# basestation_nbiot.net
KiCad netlist of a schematic drawn in EAGLE
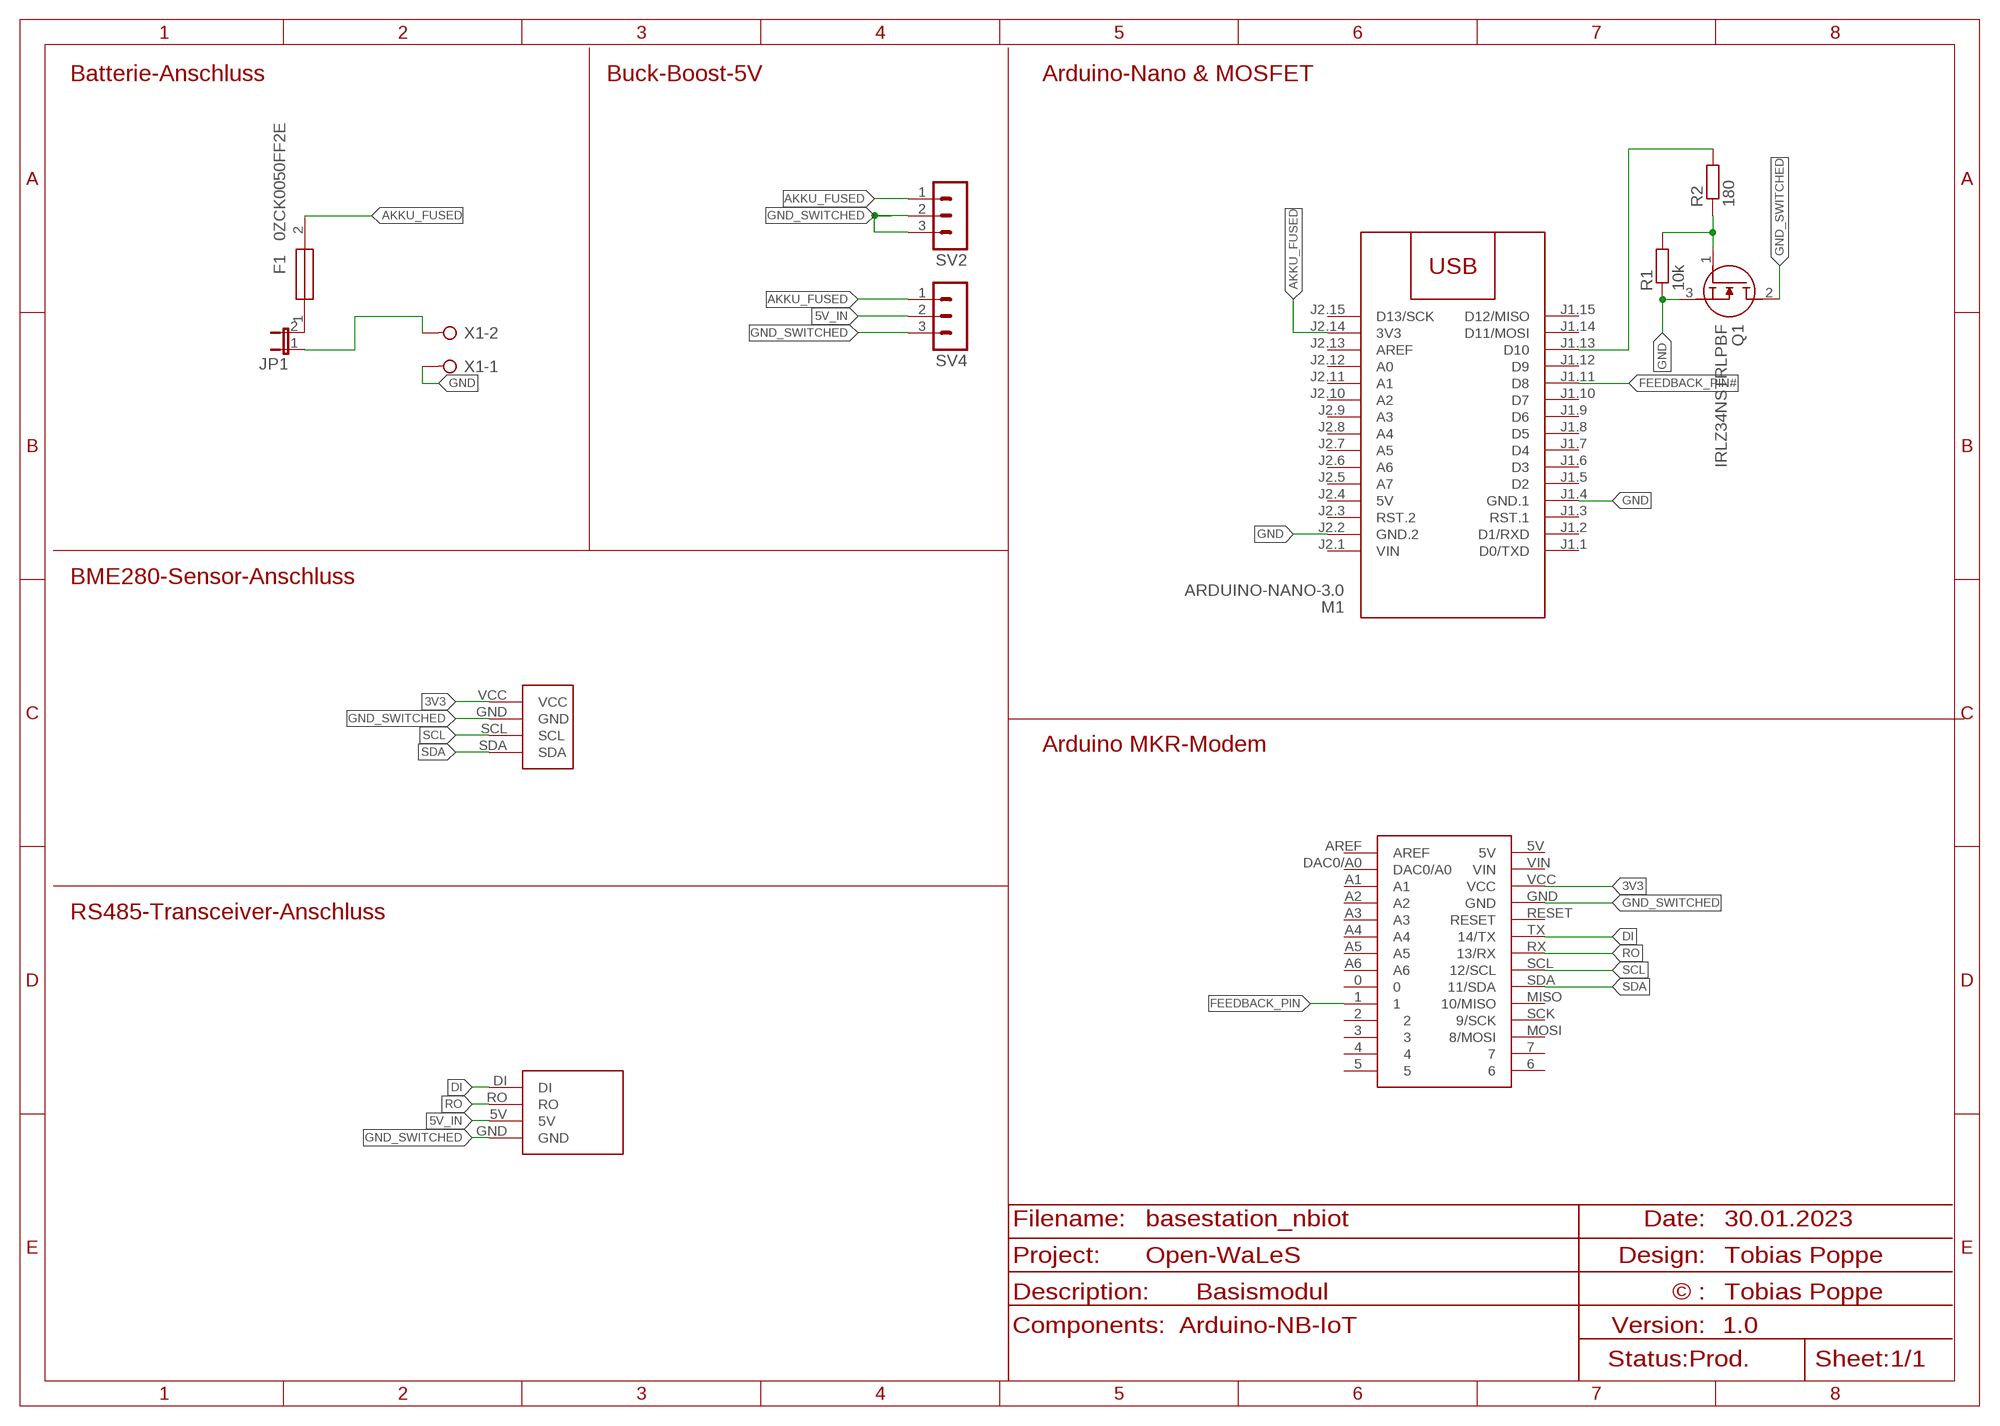
[diagram p0: schematic, sheet 1]

(export (version "E")
  (design (tool "Eeschema 10.0.6"))
  (components
    (comp (ref "F1")
      (value "0ZCK0050FF2E")
      (footprint "eagle-import:FUSC2214X125N")
      (libsource (lib "eagle-import") (part "0ZCK0050FF2E"))
    )
    (comp (ref "JP1")
      (value "JP1E")
      (footprint "eagle-import:JP1")
      (libsource (lib "eagle-import") (part "JP1E"))
    )
    (comp (ref "M1")
      (value "ARDUINO-NANO-3.0")
      (footprint "eagle-import:ARDUINO-NANO-3.0")
      (libsource (lib "eagle-import") (part "ARDUINO-NANO-3.0"))
    )
    (comp (ref "Q1")
      (value "IRLZ34NSTRLPBF")
      (footprint "eagle-import:D2PAK")
      (fields (field (name "MOUSER_PART_NUMBER") "942-IRLZ34NSTRLPBF"))
      (libsource (lib "eagle-import") (part "IRLZ34NSTRLPBF"))
    )
    (comp (ref "R1")
      (value "10k")
      (footprint "eagle-import:R1206")
      (libsource (lib "eagle-import") (part "R-EU_R1206"))
    )
    (comp (ref "R2")
      (value "180")
      (footprint "eagle-import:R1206")
      (libsource (lib "eagle-import") (part "R-EU_R1206"))
    )
    (comp (ref "SV2")
      (value "MA03-1")
      (footprint "eagle-import:MA03-1")
      (libsource (lib "eagle-import") (part "MA03-1"))
    )
    (comp (ref "SV4")
      (value "MA03-1")
      (footprint "eagle-import:MA03-1")
      (libsource (lib "eagle-import") (part "MA03-1"))
    )
    (comp (ref "U$1")
      (value "ARDUINO_GSM_MKR_1400")
      (footprint "eagle-import:ARDUINO_GSM_MKR1400")
      (libsource (lib "eagle-import") (part "ARDUINO_GSM_MKR_1400"))
    )
    (comp (ref "U$2")
      (value "BME280-BREAKOUT")
      (footprint "eagle-import:BME280-BREAKOUT")
      (libsource (lib "eagle-import") (part "BME280-BREAKOUT"))
    )
    (comp (ref "U$3")
      (value "RS485_PEGEL_BREAKOUT")
      (footprint "eagle-import:RS485_PEGEL_BREAKOUT")
      (libsource (lib "eagle-import") (part "RS485_PEGEL_BREAKOUT"))
    )
    (comp (ref "X1")
      (value "W237-02P")
      (footprint "eagle-import:W237-132")
      (libsource (lib "eagle-import") (part "W237-02P"))
    )
  )
  (nets
    (net (code "1") (name "/5V") (class "Default")
      (node (ref "M1") (pin "J2.4") (pinfunction "5V_J2.4") (pintype "power_in"))
    )
    (net (code "2") (name "/VIN") (class "Default")
      (node (ref "M1") (pin "J2.1") (pinfunction "VIN_J2.1") (pintype "power_in"))
    )
    (net (code "3") (name "3V3") (class "Default")
      (node (ref "U$1") (pin "VCC") (pinfunction "VCC_VCC") (pintype "bidirectional"))
      (node (ref "U$2") (pin "VCC") (pinfunction "VCC_VCC") (pintype "bidirectional"))
    )
    (net (code "4") (name "5V_IN") (class "Default")
      (node (ref "SV4") (pin "2") (pinfunction "2_2") (pintype "passive"))
      (node (ref "U$3") (pin "5V") (pinfunction "5V_5V") (pintype "bidirectional"))
    )
    (net (code "5") (name "AKKU_FUSED") (class "Default")
      (node (ref "F1") (pin "2") (pinfunction "2_2") (pintype "bidirectional"))
      (node (ref "M1") (pin "J2.14") (pinfunction "3V3_J2.14") (pintype "power_in"))
      (node (ref "SV2") (pin "1") (pinfunction "1_1") (pintype "passive"))
      (node (ref "SV4") (pin "1") (pinfunction "1_1") (pintype "passive"))
    )
    (net (code "6") (name "DI") (class "Default")
      (node (ref "U$1") (pin "TX") (pinfunction "14/TX_TX") (pintype "bidirectional"))
      (node (ref "U$3") (pin "DI") (pinfunction "DI_DI") (pintype "bidirectional"))
    )
    (net (code "7") (name "FEEDBACK_PIN") (class "Default")
      (node (ref "U$1") (pin "1") (pinfunction "1_1") (pintype "bidirectional"))
    )
    (net (code "8") (name "FEEDBACK_PIN#") (class "Default")
      (node (ref "M1") (pin "J1.11") (pinfunction "D8_J1.11") (pintype "bidirectional"))
    )
    (net (code "9") (name "GND") (class "Default")
      (node (ref "M1") (pin "J1.4") (pinfunction "GND.1_J1.4") (pintype "power_in"))
      (node (ref "M1") (pin "J2.2") (pinfunction "GND.2_J2.2") (pintype "power_in"))
      (node (ref "Q1") (pin "3") (pinfunction "S_3") (pintype "bidirectional"))
      (node (ref "R1") (pin "1") (pinfunction "1_1") (pintype "passive"))
      (node (ref "X1") (pin "1") (pinfunction "KL_1") (pintype "passive"))
    )
    (net (code "10") (name "GND_SWITCHED") (class "Default")
      (node (ref "Q1") (pin "2") (pinfunction "D_2") (pintype "bidirectional"))
      (node (ref "SV2") (pin "2") (pinfunction "2_2") (pintype "passive"))
      (node (ref "SV2") (pin "3") (pinfunction "3_3") (pintype "passive"))
      (node (ref "SV4") (pin "3") (pinfunction "3_3") (pintype "passive"))
      (node (ref "U$1") (pin "GND") (pinfunction "GND_GND") (pintype "bidirectional"))
      (node (ref "U$2") (pin "GND") (pinfunction "GND_GND") (pintype "bidirectional"))
      (node (ref "U$3") (pin "GND") (pinfunction "GND_GND") (pintype "bidirectional"))
    )
    (net (code "11") (name "Net-(F1-Pad1)") (class "Default")
      (node (ref "F1") (pin "1") (pinfunction "1_1") (pintype "bidirectional"))
      (node (ref "JP1") (pin "2") (pinfunction "2_2") (pintype "passive"))
    )
    (net (code "12") (name "Net-(M1-D10)") (class "Default")
      (node (ref "M1") (pin "J1.13") (pinfunction "D10_J1.13") (pintype "bidirectional"))
      (node (ref "R2") (pin "2") (pinfunction "2_2") (pintype "passive"))
    )
    (net (code "13") (name "Net-(Q1-G)") (class "Default")
      (node (ref "Q1") (pin "1") (pinfunction "G_1") (pintype "bidirectional"))
      (node (ref "R1") (pin "2") (pinfunction "2_2") (pintype "passive"))
      (node (ref "R2") (pin "1") (pinfunction "1_1") (pintype "passive"))
    )
    (net (code "14") (name "Net-(X1B-KL)") (class "Default")
      (node (ref "JP1") (pin "1") (pinfunction "1_1") (pintype "passive"))
      (node (ref "X1") (pin "2") (pinfunction "KL_2") (pintype "passive"))
    )
    (net (code "15") (name "RO") (class "Default")
      (node (ref "U$1") (pin "RX") (pinfunction "13/RX_RX") (pintype "bidirectional"))
      (node (ref "U$3") (pin "RO") (pinfunction "RO_RO") (pintype "bidirectional"))
    )
    (net (code "16") (name "SCL") (class "Default")
      (node (ref "U$1") (pin "SCL") (pinfunction "12/SCL_SCL") (pintype "bidirectional"))
      (node (ref "U$2") (pin "SCL") (pinfunction "SCL_SCL") (pintype "bidirectional"))
    )
    (net (code "17") (name "SDA") (class "Default")
      (node (ref "U$1") (pin "SDA") (pinfunction "11/SDA_SDA") (pintype "bidirectional"))
      (node (ref "U$2") (pin "SDA") (pinfunction "SDA_SDA") (pintype "bidirectional"))
    )
    (net (code "18") (name "unconnected-(M1-A0-PadJ2.12)") (class "Default")
      (node (ref "M1") (pin "J2.12") (pinfunction "A0_J2.12") (pintype "bidirectional"))
    )
    (net (code "19") (name "unconnected-(M1-A1-PadJ2.11)") (class "Default")
      (node (ref "M1") (pin "J2.11") (pinfunction "A1_J2.11") (pintype "bidirectional"))
    )
    (net (code "20") (name "unconnected-(M1-A2-PadJ2.10)") (class "Default")
      (node (ref "M1") (pin "J2.10") (pinfunction "A2_J2.10") (pintype "bidirectional"))
    )
    (net (code "21") (name "unconnected-(M1-A3-PadJ2.9)") (class "Default")
      (node (ref "M1") (pin "J2.9") (pinfunction "A3_J2.9") (pintype "bidirectional"))
    )
    (net (code "22") (name "unconnected-(M1-A4-PadJ2.8)") (class "Default")
      (node (ref "M1") (pin "J2.8") (pinfunction "A4_J2.8") (pintype "bidirectional"))
    )
    (net (code "23") (name "unconnected-(M1-A5-PadJ2.7)") (class "Default")
      (node (ref "M1") (pin "J2.7") (pinfunction "A5_J2.7") (pintype "bidirectional"))
    )
    (net (code "24") (name "unconnected-(M1-A6-PadJ2.6)") (class "Default")
      (node (ref "M1") (pin "J2.6") (pinfunction "A6_J2.6") (pintype "bidirectional"))
    )
    (net (code "25") (name "unconnected-(M1-A7-PadJ2.5)") (class "Default")
      (node (ref "M1") (pin "J2.5") (pinfunction "A7_J2.5") (pintype "bidirectional"))
    )
    (net (code "26") (name "unconnected-(M1-AREF-PadJ2.13)") (class "Default")
      (node (ref "M1") (pin "J2.13") (pinfunction "AREF_J2.13") (pintype "bidirectional"))
    )
    (net (code "27") (name "unconnected-(M1-D0{slash}TXD-PadJ1.1)") (class "Default")
      (node (ref "M1") (pin "J1.1") (pinfunction "D0/TXD_J1.1") (pintype "bidirectional"))
    )
    (net (code "28") (name "unconnected-(M1-D1{slash}RXD-PadJ1.2)") (class "Default")
      (node (ref "M1") (pin "J1.2") (pinfunction "D1/RXD_J1.2") (pintype "bidirectional"))
    )
    (net (code "29") (name "unconnected-(M1-D2-PadJ1.5)") (class "Default")
      (node (ref "M1") (pin "J1.5") (pinfunction "D2_J1.5") (pintype "bidirectional"))
    )
    (net (code "30") (name "unconnected-(M1-D3-PadJ1.6)") (class "Default")
      (node (ref "M1") (pin "J1.6") (pinfunction "D3_J1.6") (pintype "bidirectional"))
    )
    (net (code "31") (name "unconnected-(M1-D4-PadJ1.7)") (class "Default")
      (node (ref "M1") (pin "J1.7") (pinfunction "D4_J1.7") (pintype "bidirectional"))
    )
    (net (code "32") (name "unconnected-(M1-D5-PadJ1.8)") (class "Default")
      (node (ref "M1") (pin "J1.8") (pinfunction "D5_J1.8") (pintype "bidirectional"))
    )
    (net (code "33") (name "unconnected-(M1-D6-PadJ1.9)") (class "Default")
      (node (ref "M1") (pin "J1.9") (pinfunction "D6_J1.9") (pintype "bidirectional"))
    )
    (net (code "34") (name "unconnected-(M1-D7-PadJ1.10)") (class "Default")
      (node (ref "M1") (pin "J1.10") (pinfunction "D7_J1.10") (pintype "bidirectional"))
    )
    (net (code "35") (name "unconnected-(M1-D9-PadJ1.12)") (class "Default")
      (node (ref "M1") (pin "J1.12") (pinfunction "D9_J1.12") (pintype "bidirectional"))
    )
    (net (code "36") (name "unconnected-(M1-D11{slash}MOSI-PadJ1.14)") (class "Default")
      (node (ref "M1") (pin "J1.14") (pinfunction "D11/MOSI_J1.14") (pintype "bidirectional"))
    )
    (net (code "37") (name "unconnected-(M1-D12{slash}MISO-PadJ1.15)") (class "Default")
      (node (ref "M1") (pin "J1.15") (pinfunction "D12/MISO_J1.15") (pintype "bidirectional"))
    )
    (net (code "38") (name "unconnected-(M1-D13{slash}SCK-PadJ2.15)") (class "Default")
      (node (ref "M1") (pin "J2.15") (pinfunction "D13/SCK_J2.15") (pintype "bidirectional"))
    )
    (net (code "39") (name "unconnected-(M1-RST.1-PadJ1.3)") (class "Default")
      (node (ref "M1") (pin "J1.3") (pinfunction "RST.1_J1.3") (pintype "bidirectional"))
    )
    (net (code "40") (name "unconnected-(M1-RST.2-PadJ2.3)") (class "Default")
      (node (ref "M1") (pin "J2.3") (pinfunction "RST.2_J2.3") (pintype "bidirectional"))
    )
    (net (code "41") (name "unconnected-(U$1-8{slash}MOSI-PadMOSI)") (class "Default")
      (node (ref "U$1") (pin "MOSI") (pinfunction "8/MOSI_MOSI") (pintype "bidirectional"))
    )
    (net (code "42") (name "unconnected-(U$1-9{slash}SCK-PadSCK)") (class "Default")
      (node (ref "U$1") (pin "SCK") (pinfunction "9/SCK_SCK") (pintype "bidirectional"))
    )
    (net (code "43") (name "unconnected-(U$1-10{slash}MISO-PadMISO)") (class "Default")
      (node (ref "U$1") (pin "MISO") (pinfunction "10/MISO_MISO") (pintype "bidirectional"))
    )
    (net (code "44") (name "unconnected-(U$1-Pad0)") (class "Default")
      (node (ref "U$1") (pin "0") (pinfunction "0_0") (pintype "bidirectional"))
    )
    (net (code "45") (name "unconnected-(U$1-Pad5V)") (class "Default")
      (node (ref "U$1") (pin "5V") (pinfunction "5V_5V") (pintype "bidirectional"))
    )
    (net (code "46") (name "unconnected-(U$1-Pad6)") (class "Default")
      (node (ref "U$1") (pin "6") (pinfunction "6_6") (pintype "bidirectional"))
    )
    (net (code "47") (name "unconnected-(U$1-Pad7)") (class "Default")
      (node (ref "U$1") (pin "7") (pinfunction "7_7") (pintype "bidirectional"))
    )
    (net (code "48") (name "unconnected-(U$1-PadA1)") (class "Default")
      (node (ref "U$1") (pin "A1") (pinfunction "A1_A1") (pintype "bidirectional"))
    )
    (net (code "49") (name "unconnected-(U$1-PadA2)") (class "Default")
      (node (ref "U$1") (pin "A2") (pinfunction "A2_A2") (pintype "bidirectional"))
    )
    (net (code "50") (name "unconnected-(U$1-PadA3)") (class "Default")
      (node (ref "U$1") (pin "A3") (pinfunction "A3_A3") (pintype "bidirectional"))
    )
    (net (code "51") (name "unconnected-(U$1-PadA4)") (class "Default")
      (node (ref "U$1") (pin "A4") (pinfunction "A4_A4") (pintype "bidirectional"))
    )
    (net (code "52") (name "unconnected-(U$1-PadA5)") (class "Default")
      (node (ref "U$1") (pin "A5") (pinfunction "A5_A5") (pintype "bidirectional"))
    )
    (net (code "53") (name "unconnected-(U$1-PadA6)") (class "Default")
      (node (ref "U$1") (pin "A6") (pinfunction "A6_A6") (pintype "bidirectional"))
    )
    (net (code "54") (name "unconnected-(U$1-PadAREF)") (class "Default")
      (node (ref "U$1") (pin "AREF") (pinfunction "AREF_AREF") (pintype "bidirectional"))
    )
    (net (code "55") (name "unconnected-(U$1-PadDAC0{slash}A0)") (class "Default")
      (node (ref "U$1") (pin "DAC0/A0") (pinfunction "DAC0/A0_DAC0/A0") (pintype "bidirectional"))
    )
    (net (code "56") (name "unconnected-(U$1-PadRESET)") (class "Default")
      (node (ref "U$1") (pin "RESET") (pinfunction "RESET_RESET") (pintype "bidirectional"))
    )
    (net (code "57") (name "unconnected-(U$1-PadVIN)") (class "Default")
      (node (ref "U$1") (pin "VIN") (pinfunction "VIN_VIN") (pintype "bidirectional"))
    )
    (net (code "58") (name "unconnected-(U$1-⁓2-Pad2)") (class "Default")
      (node (ref "U$1") (pin "2") (pinfunction "⁓2_2") (pintype "bidirectional"))
    )
    (net (code "59") (name "unconnected-(U$1-⁓3-Pad3)") (class "Default")
      (node (ref "U$1") (pin "3") (pinfunction "⁓3_3") (pintype "bidirectional"))
    )
    (net (code "60") (name "unconnected-(U$1-⁓4-Pad4)") (class "Default")
      (node (ref "U$1") (pin "4") (pinfunction "⁓4_4") (pintype "bidirectional"))
    )
    (net (code "61") (name "unconnected-(U$1-⁓5-Pad5)") (class "Default")
      (node (ref "U$1") (pin "5") (pinfunction "⁓5_5") (pintype "bidirectional"))
    )
  )
)
